# termial.net
KiCad netlist of a schematic drawn in Altium Designer
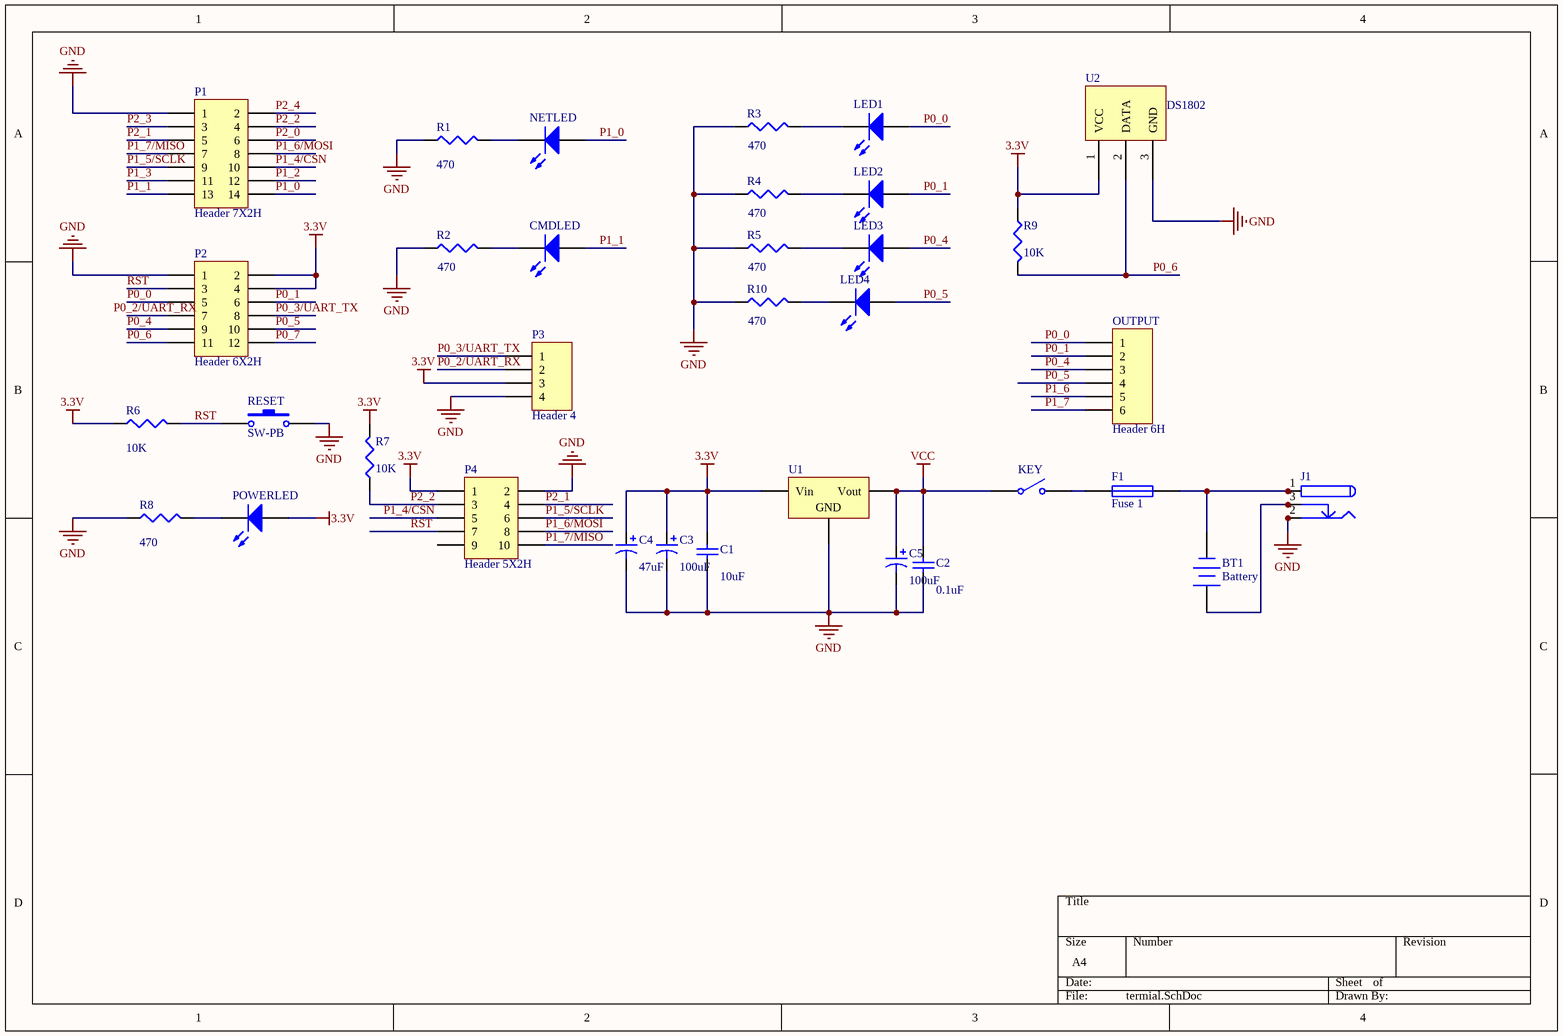
[diagram p0: termial.SchDoc]

(export (version "E")
  (design (tool "Eeschema 10.0.6"))
  (components
    (comp (ref "BT1")
      (value "Battery")
      (footprint "BAT-2")
      (description "Multicell Battery")
      (fields (field (name "PUBLISHER") "Altium Limited"))
      (libsource (lib "Miscellaneous Devices") (part "Battery"))
    )
    (comp (ref "C1")
      (value "10uF")
      (footprint "RAD-0.3")
      (description "Capacitor")
      (fields (field (name "Comment") "Cap") (field (name "PUBLISHER") "Altium Limited"))
      (libsource (lib "Miscellaneous Devices") (part "Cap"))
    )
    (comp (ref "C2")
      (value "0.1uF")
      (footprint "RAD-0.3")
      (description "Capacitor")
      (fields (field (name "Comment") "Cap") (field (name "PUBLISHER") "Altium Limited"))
      (libsource (lib "Miscellaneous Devices") (part "Cap"))
    )
    (comp (ref "C3")
      (value "100uF")
      (footprint "RB7.6-15")
      (description "Polarized Capacitor (Radial)")
      (fields (field (name "Comment") "Cap Pol1") (field (name "PUBLISHER") "Altium Limited"))
      (libsource (lib "Miscellaneous Devices") (part "Cap Pol1"))
    )
    (comp (ref "C4")
      (value "47uF")
      (footprint "RB7.6-15")
      (description "Polarized Capacitor (Radial)")
      (fields (field (name "Comment") "Cap Pol1") (field (name "PUBLISHER") "Altium Limited"))
      (libsource (lib "Miscellaneous Devices") (part "Cap Pol1"))
    )
    (comp (ref "C5")
      (value "100uF")
      (footprint "RB7.6-15")
      (description "Polarized Capacitor (Radial)")
      (fields (field (name "Comment") "Cap Pol1") (field (name "PUBLISHER") "Altium Limited"))
      (libsource (lib "Miscellaneous Devices") (part "Cap Pol1"))
    )
    (comp (ref "CMDLED")
      (value "LED1")
      (footprint "LED-1")
      (description "Typical RED GaAs LED")
      (fields (field (name "PUBLISHER") "Altium Limited"))
      (libsource (lib "Miscellaneous Devices") (part "LED1"))
    )
    (comp (ref "F1")
      (value "Fuse 1")
      (footprint "PIN-W2/E2.8")
      (description "Fuse")
      (fields (field (name "PUBLISHER") "Altium Limited"))
      (libsource (lib "Miscellaneous Devices") (part "Fuse 1"))
    )
    (comp (ref "J1")
      (value "PWR2.5")
      (footprint "KLD-0202")
      (description "Low Voltage Power Supply Connector")
      (fields (field (name "PUBLISHER") "Altium Limited"))
      (libsource (lib "Miscellaneous Connectors") (part "PWR2.5"))
    )
    (comp (ref "KEY")
      (value "SW-SPST")
      (footprint "SPST-2")
      (description "Single-Pole, Single-Throw Switch")
      (fields (field (name "PUBLISHER") "Altium Limited"))
      (libsource (lib "Miscellaneous Devices") (part "SW-SPST"))
    )
    (comp (ref "LED1")
      (value "LED1")
      (footprint "LED-1")
      (description "Typical RED GaAs LED")
      (fields (field (name "PUBLISHER") "Altium Limited"))
      (libsource (lib "Miscellaneous Devices") (part "LED1"))
    )
    (comp (ref "LED2")
      (value "LED1")
      (footprint "LED-1")
      (description "Typical RED GaAs LED")
      (fields (field (name "PUBLISHER") "Altium Limited"))
      (libsource (lib "Miscellaneous Devices") (part "LED1"))
    )
    (comp (ref "LED3")
      (value "LED1")
      (footprint "LED-1")
      (description "Typical RED GaAs LED")
      (fields (field (name "PUBLISHER") "Altium Limited"))
      (libsource (lib "Miscellaneous Devices") (part "LED1"))
    )
    (comp (ref "LED4")
      (value "LED3")
      (footprint "3.5X2.8X1.9")
      (description "Typical BLUE SiC LED")
      (fields (field (name "PUBLISHER") "Altium Limited"))
      (libsource (lib "Miscellaneous Devices") (part "LED3"))
    )
    (comp (ref "NETLED")
      (value "LED1")
      (footprint "LED-1")
      (description "Typical RED GaAs LED")
      (fields (field (name "PUBLISHER") "Altium Limited"))
      (libsource (lib "Miscellaneous Devices") (part "LED1"))
    )
    (comp (ref "OUTPUT")
      (value "Header 6H")
      (footprint "HDR1X6H")
      (description "Header, 6-Pin, Right Angle")
      (fields (field (name "PUBLISHER") "Altium Limited"))
      (libsource (lib "Miscellaneous Connectors") (part "Header 6H"))
    )
    (comp (ref "P1")
      (value "Header 7X2H")
      (footprint "HDR2X7H")
      (description "Header, 7-Pin, Dual row, Right Angle")
      (fields (field (name "PUBLISHER") "Altium Limited"))
      (libsource (lib "Miscellaneous Connectors") (part "Header 7X2H"))
    )
    (comp (ref "P2")
      (value "Header 6X2H")
      (footprint "HDR2X6H")
      (description "Header, 6-Pin, Dual row, Right Angle")
      (fields (field (name "PUBLISHER") "Altium Limited"))
      (libsource (lib "Miscellaneous Connectors") (part "Header 6X2H"))
    )
    (comp (ref "P3")
      (value "Header 4")
      (footprint "HDR1X4")
      (description "Header, 4-Pin")
      (fields (field (name "PUBLISHER") "Altium Limited"))
      (libsource (lib "Miscellaneous Connectors") (part "Header 4"))
    )
    (comp (ref "P4")
      (value "Header 5X2H")
      (footprint "HDR2X5H")
      (description "Header, 5-Pin, Dual row, Right Angle")
      (fields (field (name "PUBLISHER") "Altium Limited"))
      (libsource (lib "Miscellaneous Connectors") (part "Header 5X2H"))
    )
    (comp (ref "POWERLED")
      (value "LED1")
      (footprint "LED-1")
      (description "Typical RED GaAs LED")
      (fields (field (name "PUBLISHER") "Altium Limited"))
      (libsource (lib "Miscellaneous Devices") (part "LED1"))
    )
    (comp (ref "R1")
      (value "470")
      (footprint "J1-0603")
      (description "Resistor")
      (fields (field (name "Comment") "Res3") (field (name "PUBLISHER") "Altium Limited"))
      (libsource (lib "Miscellaneous Devices") (part "Res3"))
    )
    (comp (ref "R2")
      (value "470")
      (footprint "J1-0603")
      (description "Resistor")
      (fields (field (name "Comment") "Res3") (field (name "PUBLISHER") "Altium Limited"))
      (libsource (lib "Miscellaneous Devices") (part "Res3"))
    )
    (comp (ref "R3")
      (value "470")
      (footprint "J1-0603")
      (description "Resistor")
      (fields (field (name "Comment") "Res3") (field (name "PUBLISHER") "Altium Limited"))
      (libsource (lib "Miscellaneous Devices") (part "Res3"))
    )
    (comp (ref "R4")
      (value "470")
      (footprint "J1-0603")
      (description "Resistor")
      (fields (field (name "Comment") "Res3") (field (name "PUBLISHER") "Altium Limited"))
      (libsource (lib "Miscellaneous Devices") (part "Res3"))
    )
    (comp (ref "R5")
      (value "470")
      (footprint "J1-0603")
      (description "Resistor")
      (fields (field (name "Comment") "Res3") (field (name "PUBLISHER") "Altium Limited"))
      (libsource (lib "Miscellaneous Devices") (part "Res3"))
    )
    (comp (ref "R6")
      (value "10K")
      (footprint "J1-0603")
      (description "Resistor")
      (fields (field (name "Comment") "Res3") (field (name "PUBLISHER") "Altium Limited"))
      (libsource (lib "Miscellaneous Devices") (part "Res3"))
    )
    (comp (ref "R7")
      (value "10K")
      (footprint "J1-0603")
      (description "Resistor")
      (fields (field (name "Comment") "Res3") (field (name "PUBLISHER") "Altium Limited"))
      (libsource (lib "Miscellaneous Devices") (part "Res3"))
    )
    (comp (ref "R8")
      (value "470")
      (footprint "J1-0603")
      (description "Resistor")
      (fields (field (name "Comment") "Res3") (field (name "PUBLISHER") "Altium Limited"))
      (libsource (lib "Miscellaneous Devices") (part "Res3"))
    )
    (comp (ref "R9")
      (value "10K")
      (footprint "J1-0603")
      (description "Resistor")
      (fields (field (name "Comment") "Res3") (field (name "PUBLISHER") "Altium Limited"))
      (libsource (lib "Miscellaneous Devices") (part "Res3"))
    )
    (comp (ref "R10")
      (value "470")
      (footprint "J1-0603")
      (description "Resistor")
      (fields (field (name "Comment") "Res3") (field (name "PUBLISHER") "Altium Limited"))
      (libsource (lib "Miscellaneous Devices") (part "Res3"))
    )
    (comp (ref "RESET")
      (value "SW-PB")
      (footprint "SPST-2")
      (description "Switch")
      (fields (field (name "PUBLISHER") "Altium Limited"))
      (libsource (lib "Miscellaneous Devices") (part "SW-PB"))
    )
    (comp (ref "U1")
      (value "Volt Reg")
      (footprint "D2PAK_N")
      (description "Voltage Regulator")
      (fields (field (name "PUBLISHER") "Altium Limited"))
      (libsource (lib "Miscellaneous Devices") (part "Volt Reg"))
    )
    (comp (ref "U2") (value "DS1802") (libsource (lib "zigbee") (part "DS1802")))
  )
  (nets
    (net (code "1") (name "/P0_0") (class "Default")
      (node (ref "LED1") (pin "1") (pinfunction "A_1") (pintype "passive"))
      (node (ref "OUTPUT") (pin "1") (pinfunction "1_1") (pintype "passive"))
      (node (ref "P2") (pin "5") (pinfunction "5_5") (pintype "passive"))
    )
    (net (code "2") (name "/P0_1") (class "Default")
      (node (ref "LED2") (pin "1") (pinfunction "A_1") (pintype "passive"))
      (node (ref "OUTPUT") (pin "2") (pinfunction "2_2") (pintype "passive"))
      (node (ref "P2") (pin "6") (pinfunction "6_6") (pintype "passive"))
    )
    (net (code "3") (name "/P0_2{slash}UART_RX") (class "Default")
      (node (ref "P3") (pin "2") (pinfunction "2_2") (pintype "passive"))
    )
    (net (code "4") (name "/P0_3{slash}UART_TX") (class "Default")
      (node (ref "P2") (pin "8") (pinfunction "8_8") (pintype "passive"))
      (node (ref "P3") (pin "1") (pinfunction "1_1") (pintype "passive"))
    )
    (net (code "5") (name "/P0_4") (class "Default")
      (node (ref "LED3") (pin "1") (pinfunction "A_1") (pintype "passive"))
      (node (ref "OUTPUT") (pin "3") (pinfunction "3_3") (pintype "passive"))
      (node (ref "P2") (pin "9") (pinfunction "9_9") (pintype "passive"))
    )
    (net (code "6") (name "/P0_5") (class "Default")
      (node (ref "LED4") (pin "1") (pinfunction "A_1") (pintype "passive"))
      (node (ref "OUTPUT") (pin "4") (pinfunction "4_4") (pintype "passive"))
      (node (ref "P2") (pin "10") (pinfunction "10_10") (pintype "passive"))
    )
    (net (code "7") (name "/P0_6") (class "Default")
      (node (ref "P2") (pin "11") (pinfunction "11_11") (pintype "passive"))
      (node (ref "R9") (pin "2") (pinfunction "2_2") (pintype "passive"))
      (node (ref "U2") (pin "2") (pinfunction "DATA_2") (pintype "passive"))
    )
    (net (code "8") (name "/P0_7") (class "Default")
      (node (ref "P2") (pin "12") (pinfunction "12_12") (pintype "passive"))
    )
    (net (code "9") (name "/P1_0") (class "Default")
      (node (ref "NETLED") (pin "1") (pinfunction "A_1") (pintype "passive"))
      (node (ref "P1") (pin "14") (pinfunction "14_14") (pintype "passive"))
    )
    (net (code "10") (name "/P1_1") (class "Default")
      (node (ref "CMDLED") (pin "1") (pinfunction "A_1") (pintype "passive"))
      (node (ref "P1") (pin "13") (pinfunction "13_13") (pintype "passive"))
    )
    (net (code "11") (name "/P1_2") (class "Default")
      (node (ref "P1") (pin "12") (pinfunction "12_12") (pintype "passive"))
    )
    (net (code "12") (name "/P1_3") (class "Default")
      (node (ref "P1") (pin "11") (pinfunction "11_11") (pintype "passive"))
    )
    (net (code "13") (name "/P1_4{slash}CSN") (class "Default")
      (node (ref "P1") (pin "10") (pinfunction "10_10") (pintype "passive"))
      (node (ref "P4") (pin "5") (pinfunction "5_5") (pintype "passive"))
    )
    (net (code "14") (name "/P1_5{slash}SCLK") (class "Default")
      (node (ref "P1") (pin "9") (pinfunction "9_9") (pintype "passive"))
      (node (ref "P4") (pin "6") (pinfunction "6_6") (pintype "passive"))
    )
    (net (code "15") (name "/P1_6") (class "Default")
      (node (ref "OUTPUT") (pin "5") (pinfunction "5_5") (pintype "passive"))
    )
    (net (code "16") (name "/P1_6{slash}MOSI") (class "Default")
      (node (ref "P1") (pin "8") (pinfunction "8_8") (pintype "passive"))
      (node (ref "P4") (pin "8") (pinfunction "8_8") (pintype "passive"))
    )
    (net (code "17") (name "/P1_7") (class "Default")
      (node (ref "OUTPUT") (pin "6") (pinfunction "6_6") (pintype "passive"))
    )
    (net (code "18") (name "/P1_7{slash}MISO") (class "Default")
      (node (ref "P1") (pin "7") (pinfunction "7_7") (pintype "passive"))
      (node (ref "P4") (pin "10") (pinfunction "10_10") (pintype "passive"))
    )
    (net (code "19") (name "/P2_0") (class "Default")
      (node (ref "P1") (pin "6") (pinfunction "6_6") (pintype "passive"))
    )
    (net (code "20") (name "/P2_1") (class "Default")
      (node (ref "P1") (pin "5") (pinfunction "5_5") (pintype "passive"))
      (node (ref "P4") (pin "4") (pinfunction "4_4") (pintype "passive"))
    )
    (net (code "21") (name "/P2_2") (class "Default")
      (node (ref "P1") (pin "4") (pinfunction "4_4") (pintype "passive"))
      (node (ref "P4") (pin "3") (pinfunction "3_3") (pintype "passive"))
      (node (ref "R7") (pin "1") (pinfunction "1_1") (pintype "passive"))
    )
    (net (code "22") (name "/P2_3") (class "Default")
      (node (ref "P1") (pin "3") (pinfunction "3_3") (pintype "passive"))
    )
    (net (code "23") (name "/P2_4") (class "Default")
      (node (ref "P1") (pin "2") (pinfunction "2_2") (pintype "passive"))
    )
    (net (code "24") (name "/RST") (class "Default")
      (node (ref "P2") (pin "3") (pinfunction "3_3") (pintype "passive"))
      (node (ref "P4") (pin "7") (pinfunction "7_7") (pintype "passive"))
      (node (ref "R6") (pin "2") (pinfunction "2_2") (pintype "passive"))
      (node (ref "RESET") (pin "1") (pinfunction "1_1") (pintype "passive"))
    )
    (net (code "25") (name "3.3V") (class "Default")
      (node (ref "C1") (pin "2") (pinfunction "2_2") (pintype "passive"))
      (node (ref "C3") (pin "1") (pinfunction "1_1") (pintype "passive"))
      (node (ref "C4") (pin "1") (pinfunction "1_1") (pintype "passive"))
      (node (ref "P2") (pin "2") (pinfunction "2_2") (pintype "passive"))
      (node (ref "P2") (pin "4") (pinfunction "4_4") (pintype "passive"))
      (node (ref "P3") (pin "3") (pinfunction "3_3") (pintype "passive"))
      (node (ref "P4") (pin "1") (pinfunction "1_1") (pintype "passive"))
      (node (ref "POWERLED") (pin "1") (pinfunction "A_1") (pintype "passive"))
      (node (ref "R6") (pin "1") (pinfunction "1_1") (pintype "passive"))
      (node (ref "R7") (pin "2") (pinfunction "2_2") (pintype "passive"))
      (node (ref "R9") (pin "1") (pinfunction "1_1") (pintype "passive"))
      (node (ref "U1") (pin "1") (pinfunction "Vin_1") (pintype "passive"))
      (node (ref "U2") (pin "1") (pinfunction "VCC_1") (pintype "passive"))
    )
    (net (code "26") (name "GND") (class "Default")
      (node (ref "C1") (pin "1") (pinfunction "1_1") (pintype "passive"))
      (node (ref "C2") (pin "1") (pinfunction "1_1") (pintype "passive"))
      (node (ref "C3") (pin "2") (pinfunction "2_2") (pintype "passive"))
      (node (ref "C4") (pin "2") (pinfunction "2_2") (pintype "passive"))
      (node (ref "C5") (pin "2") (pinfunction "2_2") (pintype "passive"))
      (node (ref "J1") (pin "2") (pinfunction "2_2") (pintype "power_in"))
      (node (ref "J1") (pin "2A") (pinfunction "2A_2A") (pintype "power_in"))
      (node (ref "J1") (pin "2B") (pinfunction "2B_2B") (pintype "power_in"))
      (node (ref "P1") (pin "1") (pinfunction "1_1") (pintype "passive"))
      (node (ref "P2") (pin "1") (pinfunction "1_1") (pintype "passive"))
      (node (ref "P3") (pin "4") (pinfunction "4_4") (pintype "passive"))
      (node (ref "P4") (pin "2") (pinfunction "2_2") (pintype "passive"))
      (node (ref "R1") (pin "1") (pinfunction "1_1") (pintype "passive"))
      (node (ref "R10") (pin "1") (pinfunction "1_1") (pintype "passive"))
      (node (ref "R2") (pin "1") (pinfunction "1_1") (pintype "passive"))
      (node (ref "R3") (pin "1") (pinfunction "1_1") (pintype "passive"))
      (node (ref "R4") (pin "1") (pinfunction "1_1") (pintype "passive"))
      (node (ref "R5") (pin "1") (pinfunction "1_1") (pintype "passive"))
      (node (ref "R8") (pin "1") (pinfunction "1_1") (pintype "passive"))
      (node (ref "RESET") (pin "2") (pinfunction "2_2") (pintype "passive"))
      (node (ref "U1") (pin "2") (pinfunction "GND_2") (pintype "passive"))
      (node (ref "U2") (pin "3") (pinfunction "GND_3") (pintype "passive"))
    )
    (net (code "27") (name "Net-(BT1-+)") (class "Default")
      (node (ref "BT1") (pin "1") (pinfunction "+_1") (pintype "passive"))
      (node (ref "J1") (pin "3") (pinfunction "3_3") (pintype "power_in"))
      (node (ref "J1") (pin "3A") (pinfunction "3A_3A") (pintype "power_in"))
      (node (ref "J1") (pin "3B") (pinfunction "3B_3B") (pintype "power_in"))
    )
    (net (code "28") (name "Net-(BT1--)") (class "Default")
      (node (ref "BT1") (pin "2") (pinfunction "-_2") (pintype "passive"))
      (node (ref "F1") (pin "2") (pinfunction "2_2") (pintype "passive"))
      (node (ref "J1") (pin "1") (pinfunction "1_1") (pintype "power_in"))
      (node (ref "J1") (pin "1A") (pinfunction "1A_1A") (pintype "power_in"))
      (node (ref "J1") (pin "1B") (pinfunction "1B_1B") (pintype "power_in"))
    )
    (net (code "29") (name "Net-(CMDLED-K)") (class "Default")
      (node (ref "CMDLED") (pin "2") (pinfunction "K_2") (pintype "passive"))
      (node (ref "R2") (pin "2") (pinfunction "2_2") (pintype "passive"))
    )
    (net (code "30") (name "Net-(KEY-NO)") (class "Default")
      (node (ref "F1") (pin "1") (pinfunction "1_1") (pintype "passive"))
      (node (ref "KEY") (pin "2") (pinfunction "NO_2") (pintype "passive"))
    )
    (net (code "31") (name "Net-(LED1-K)") (class "Default")
      (node (ref "LED1") (pin "2") (pinfunction "K_2") (pintype "passive"))
      (node (ref "R3") (pin "2") (pinfunction "2_2") (pintype "passive"))
    )
    (net (code "32") (name "Net-(LED2-K)") (class "Default")
      (node (ref "LED2") (pin "2") (pinfunction "K_2") (pintype "passive"))
      (node (ref "R4") (pin "2") (pinfunction "2_2") (pintype "passive"))
    )
    (net (code "33") (name "Net-(LED3-K)") (class "Default")
      (node (ref "LED3") (pin "2") (pinfunction "K_2") (pintype "passive"))
      (node (ref "R5") (pin "2") (pinfunction "2_2") (pintype "passive"))
    )
    (net (code "34") (name "Net-(LED4-K)") (class "Default")
      (node (ref "LED4") (pin "2") (pinfunction "K_2") (pintype "passive"))
      (node (ref "R10") (pin "2") (pinfunction "2_2") (pintype "passive"))
    )
    (net (code "35") (name "Net-(NETLED-K)") (class "Default")
      (node (ref "NETLED") (pin "2") (pinfunction "K_2") (pintype "passive"))
      (node (ref "R1") (pin "2") (pinfunction "2_2") (pintype "passive"))
    )
    (net (code "36") (name "Net-(POWERLED-K)") (class "Default")
      (node (ref "POWERLED") (pin "2") (pinfunction "K_2") (pintype "passive"))
      (node (ref "R8") (pin "2") (pinfunction "2_2") (pintype "passive"))
    )
    (net (code "37") (name "VCC") (class "Default")
      (node (ref "C2") (pin "2") (pinfunction "2_2") (pintype "passive"))
      (node (ref "C5") (pin "1") (pinfunction "1_1") (pintype "passive"))
      (node (ref "KEY") (pin "1") (pinfunction "COMMON_1") (pintype "passive"))
      (node (ref "U1") (pin "3") (pinfunction "Vout_3") (pintype "passive"))
    )
    (net (code "38") (name "unconnected-(P2-Pad7)") (class "Default")
      (node (ref "P2") (pin "7") (pinfunction "7_7") (pintype "passive"))
    )
    (net (code "39") (name "unconnected-(P4-Pad9)") (class "Default")
      (node (ref "P4") (pin "9") (pinfunction "9_9") (pintype "passive"))
    )
  )
)
